# SCH_nfc-card_2024-08-05.net
KiCad netlist of a schematic drawn in EasyEDA
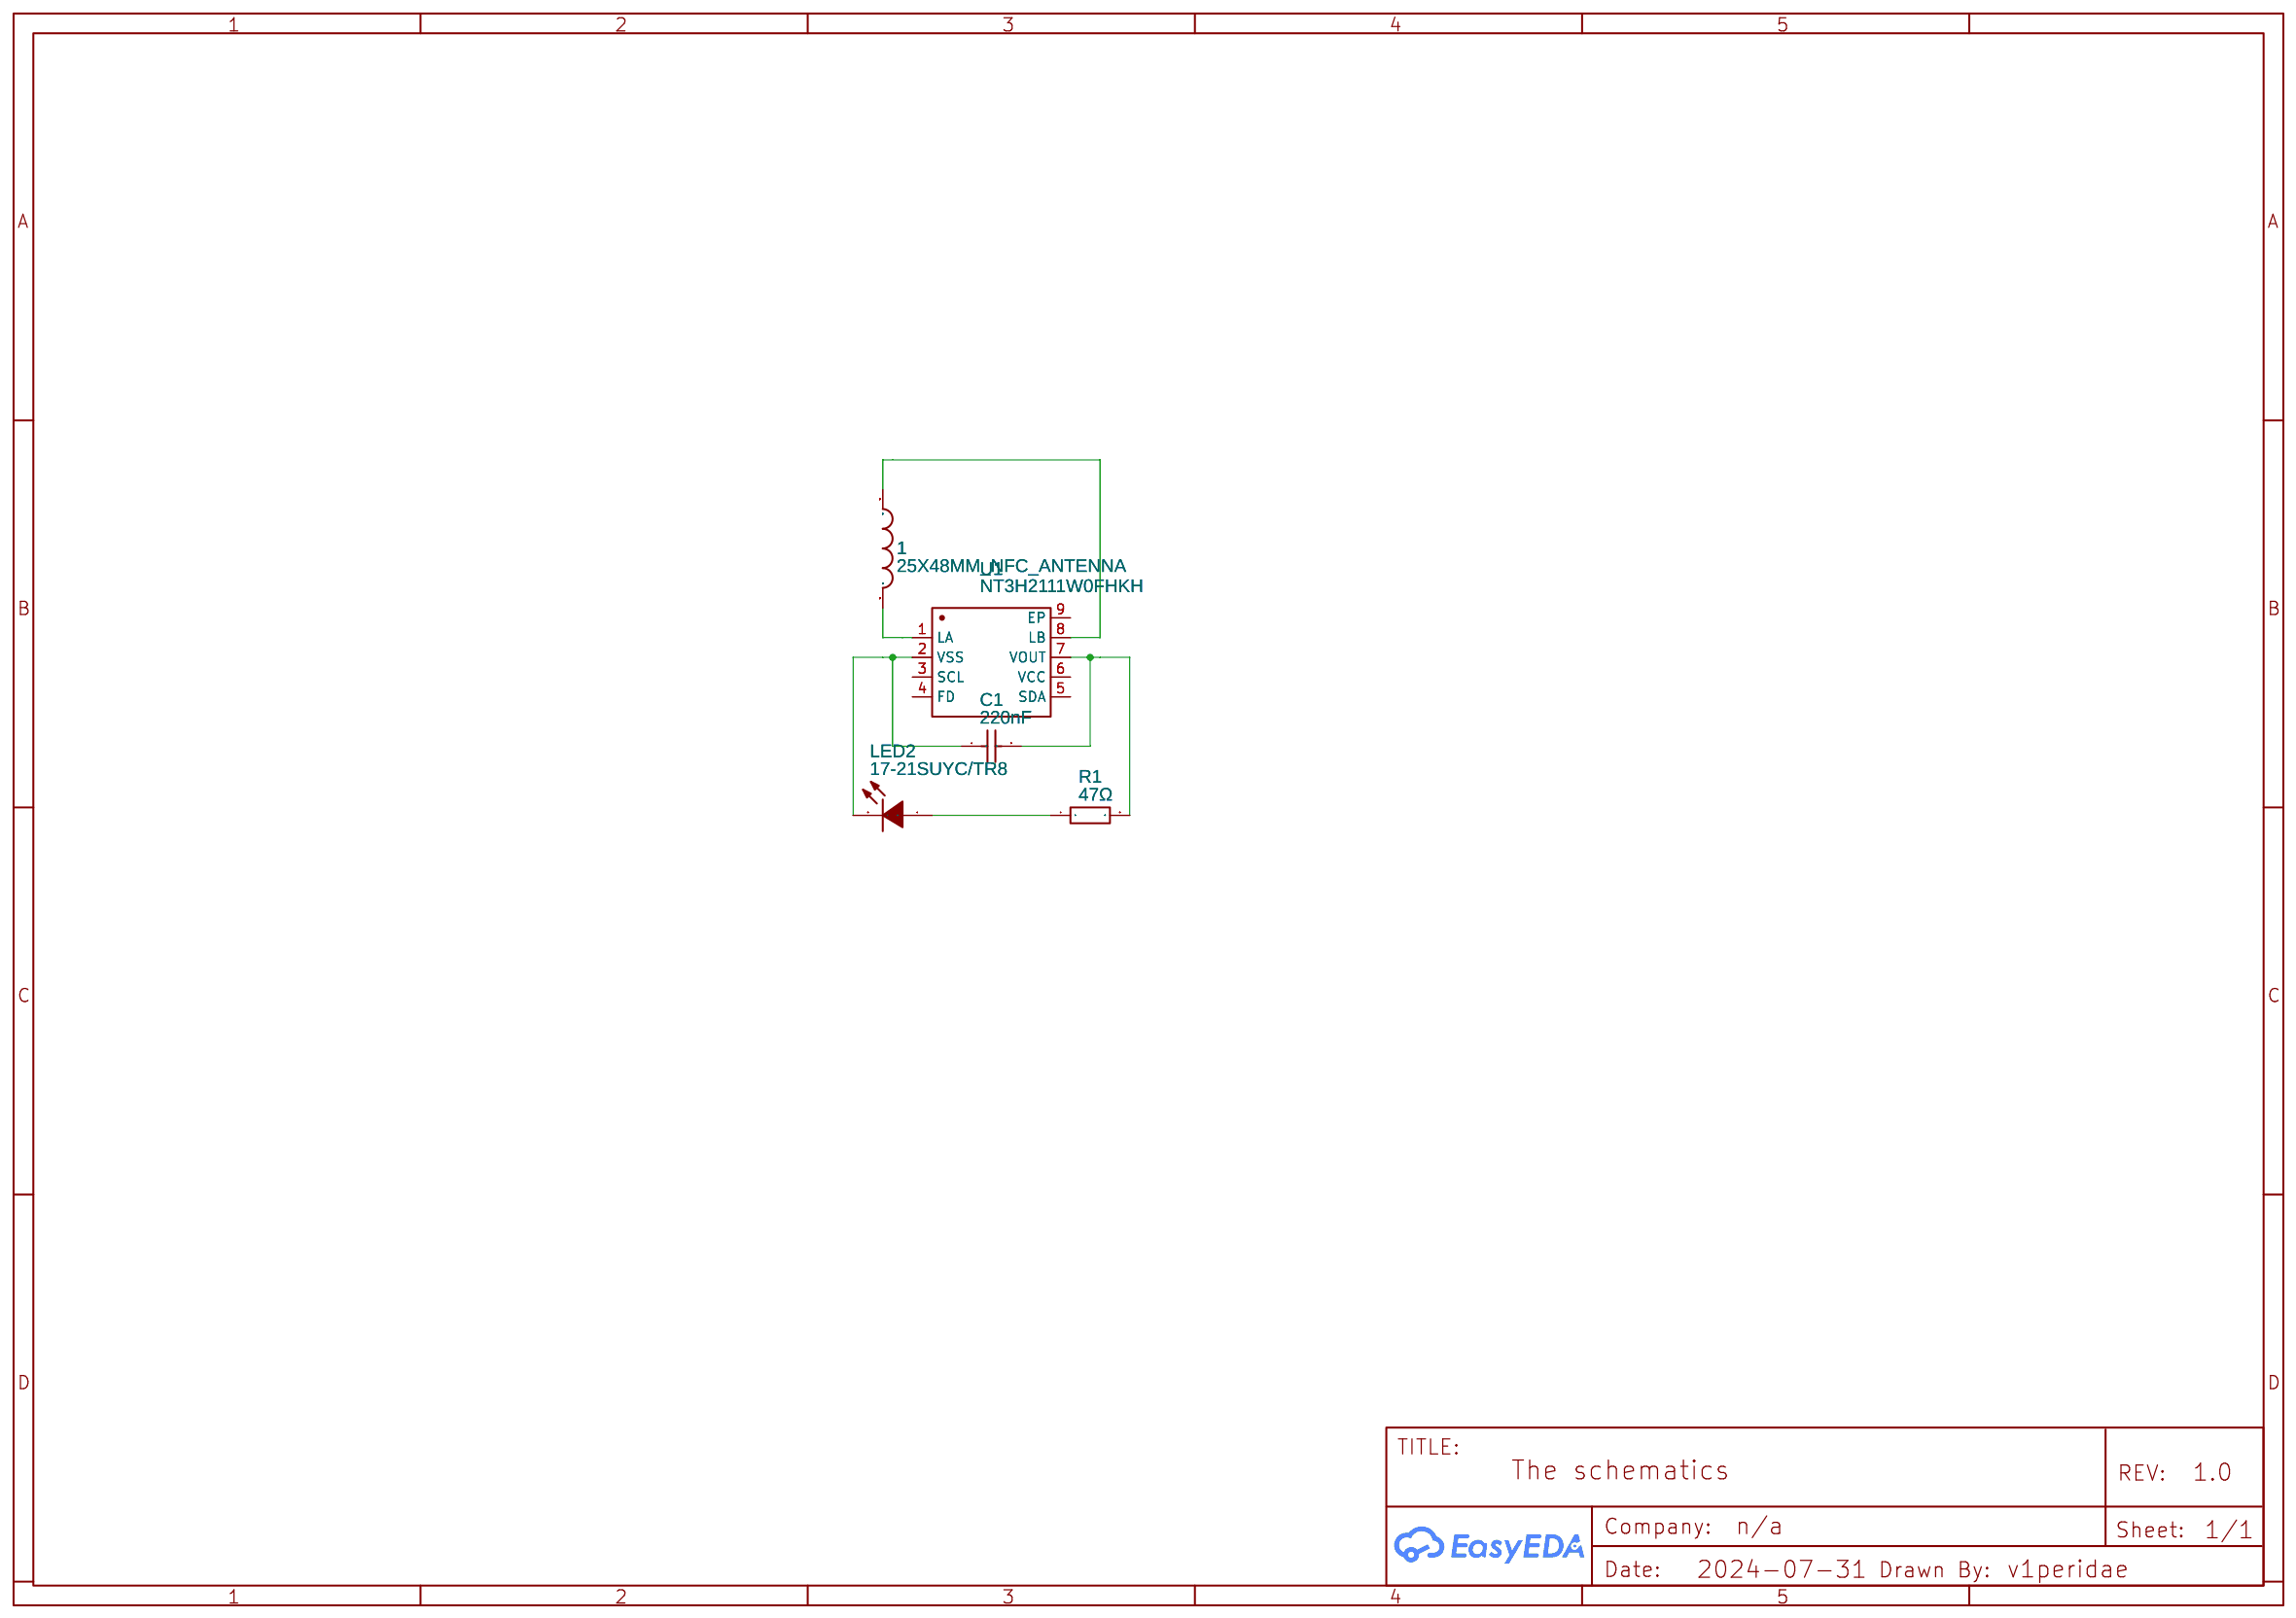
[diagram p0: schematic sheet]

(export (version "E")
  (design (tool "Eeschema 10.0.6"))
  (components
    (comp (ref "1") (value "25X48MM_NFC_ANTENNA") (libsource (lib "") (part "25X48MM_NFC_ANTENNA")))
    (comp (ref "C1")
      (value "220nF")
      (fields
        (field (name "Manufacturer Part") "CL10B224KA8NNNC")
        (field (name "Manufacturer") "SAMSUNG(三星)")
      )
      (libsource (lib "") (part "CL10B224KA8NNNC"))
    )
    (comp (ref "LED2")
      (value "17-21SUYC/TR8")
      (fields (field (name "Manufacturer Part") "KT-0805黄灯") (field (name "Manufacturer") "KENTO"))
      (libsource (lib "") (part "17-21SUYC/TR8"))
    )
    (comp (ref "R1")
      (value "47Ω")
      (fields
        (field (name "Manufacturer Part") "0603WAF470JT5E")
        (field (name "Manufacturer") "UNI-ROYAL(厚声)")
      )
      (libsource (lib "") (part "0603WAF470JT5E"))
    )
    (comp (ref "U1")
      (value "NT3H2111W0FHKH")
      (fields (field (name "Manufacturer") "NXP(恩智浦)"))
      (libsource (lib "") (part "NT3H2111W0FHKH"))
    )
  )
  (nets
    (net (code "1") (name "Net-(LED2-+)") (class "Default")
      (node (ref "LED2") (pin "1") (pinfunction "+_1") (pintype "unspecified"))
      (node (ref "R1") (pin "1") (pinfunction "1_1") (pintype "input"))
    )
    (net (code "2") (name "Net-(LED2--)") (class "Default")
      (node (ref "C1") (pin "1") (pinfunction "1_1") (pintype "input"))
      (node (ref "LED2") (pin "2") (pinfunction "-_2") (pintype "unspecified"))
      (node (ref "U1") (pin "2") (pinfunction "VSS_2") (pintype "unspecified"))
    )
    (net (code "3") (name "Net-(U1-LA)") (class "Default")
      (node (ref "1") (pin "P$2") (pinfunction "P$2_P$2") (pintype "bidirectional"))
      (node (ref "U1") (pin "1") (pinfunction "LA_1") (pintype "unspecified"))
    )
    (net (code "4") (name "Net-(U1-LB)") (class "Default")
      (node (ref "1") (pin "P$1") (pinfunction "P$1_P$1") (pintype "bidirectional"))
      (node (ref "U1") (pin "8") (pinfunction "LB_8") (pintype "unspecified"))
    )
    (net (code "5") (name "Net-(U1-VOUT)") (class "Default")
      (node (ref "C1") (pin "2") (pinfunction "2_2") (pintype "input"))
      (node (ref "R1") (pin "2") (pinfunction "2_2") (pintype "input"))
      (node (ref "U1") (pin "7") (pinfunction "VOUT_7") (pintype "unspecified"))
    )
    (net (code "6") (name "unconnected-(U1-EP-Pad9)") (class "Default")
      (node (ref "U1") (pin "9") (pinfunction "EP_9") (pintype "unspecified"))
    )
    (net (code "7") (name "unconnected-(U1-FD-Pad4)") (class "Default")
      (node (ref "U1") (pin "4") (pinfunction "FD_4") (pintype "unspecified"))
    )
    (net (code "8") (name "unconnected-(U1-SCL-Pad3)") (class "Default")
      (node (ref "U1") (pin "3") (pinfunction "SCL_3") (pintype "unspecified"))
    )
    (net (code "9") (name "unconnected-(U1-SDA-Pad5)") (class "Default")
      (node (ref "U1") (pin "5") (pinfunction "SDA_5") (pintype "unspecified"))
    )
    (net (code "10") (name "unconnected-(U1-VCC-Pad6)") (class "Default")
      (node (ref "U1") (pin "6") (pinfunction "VCC_6") (pintype "unspecified"))
    )
  )
)
